# Single_Board_12s.net
KiCad netlist of a schematic drawn in EAGLE
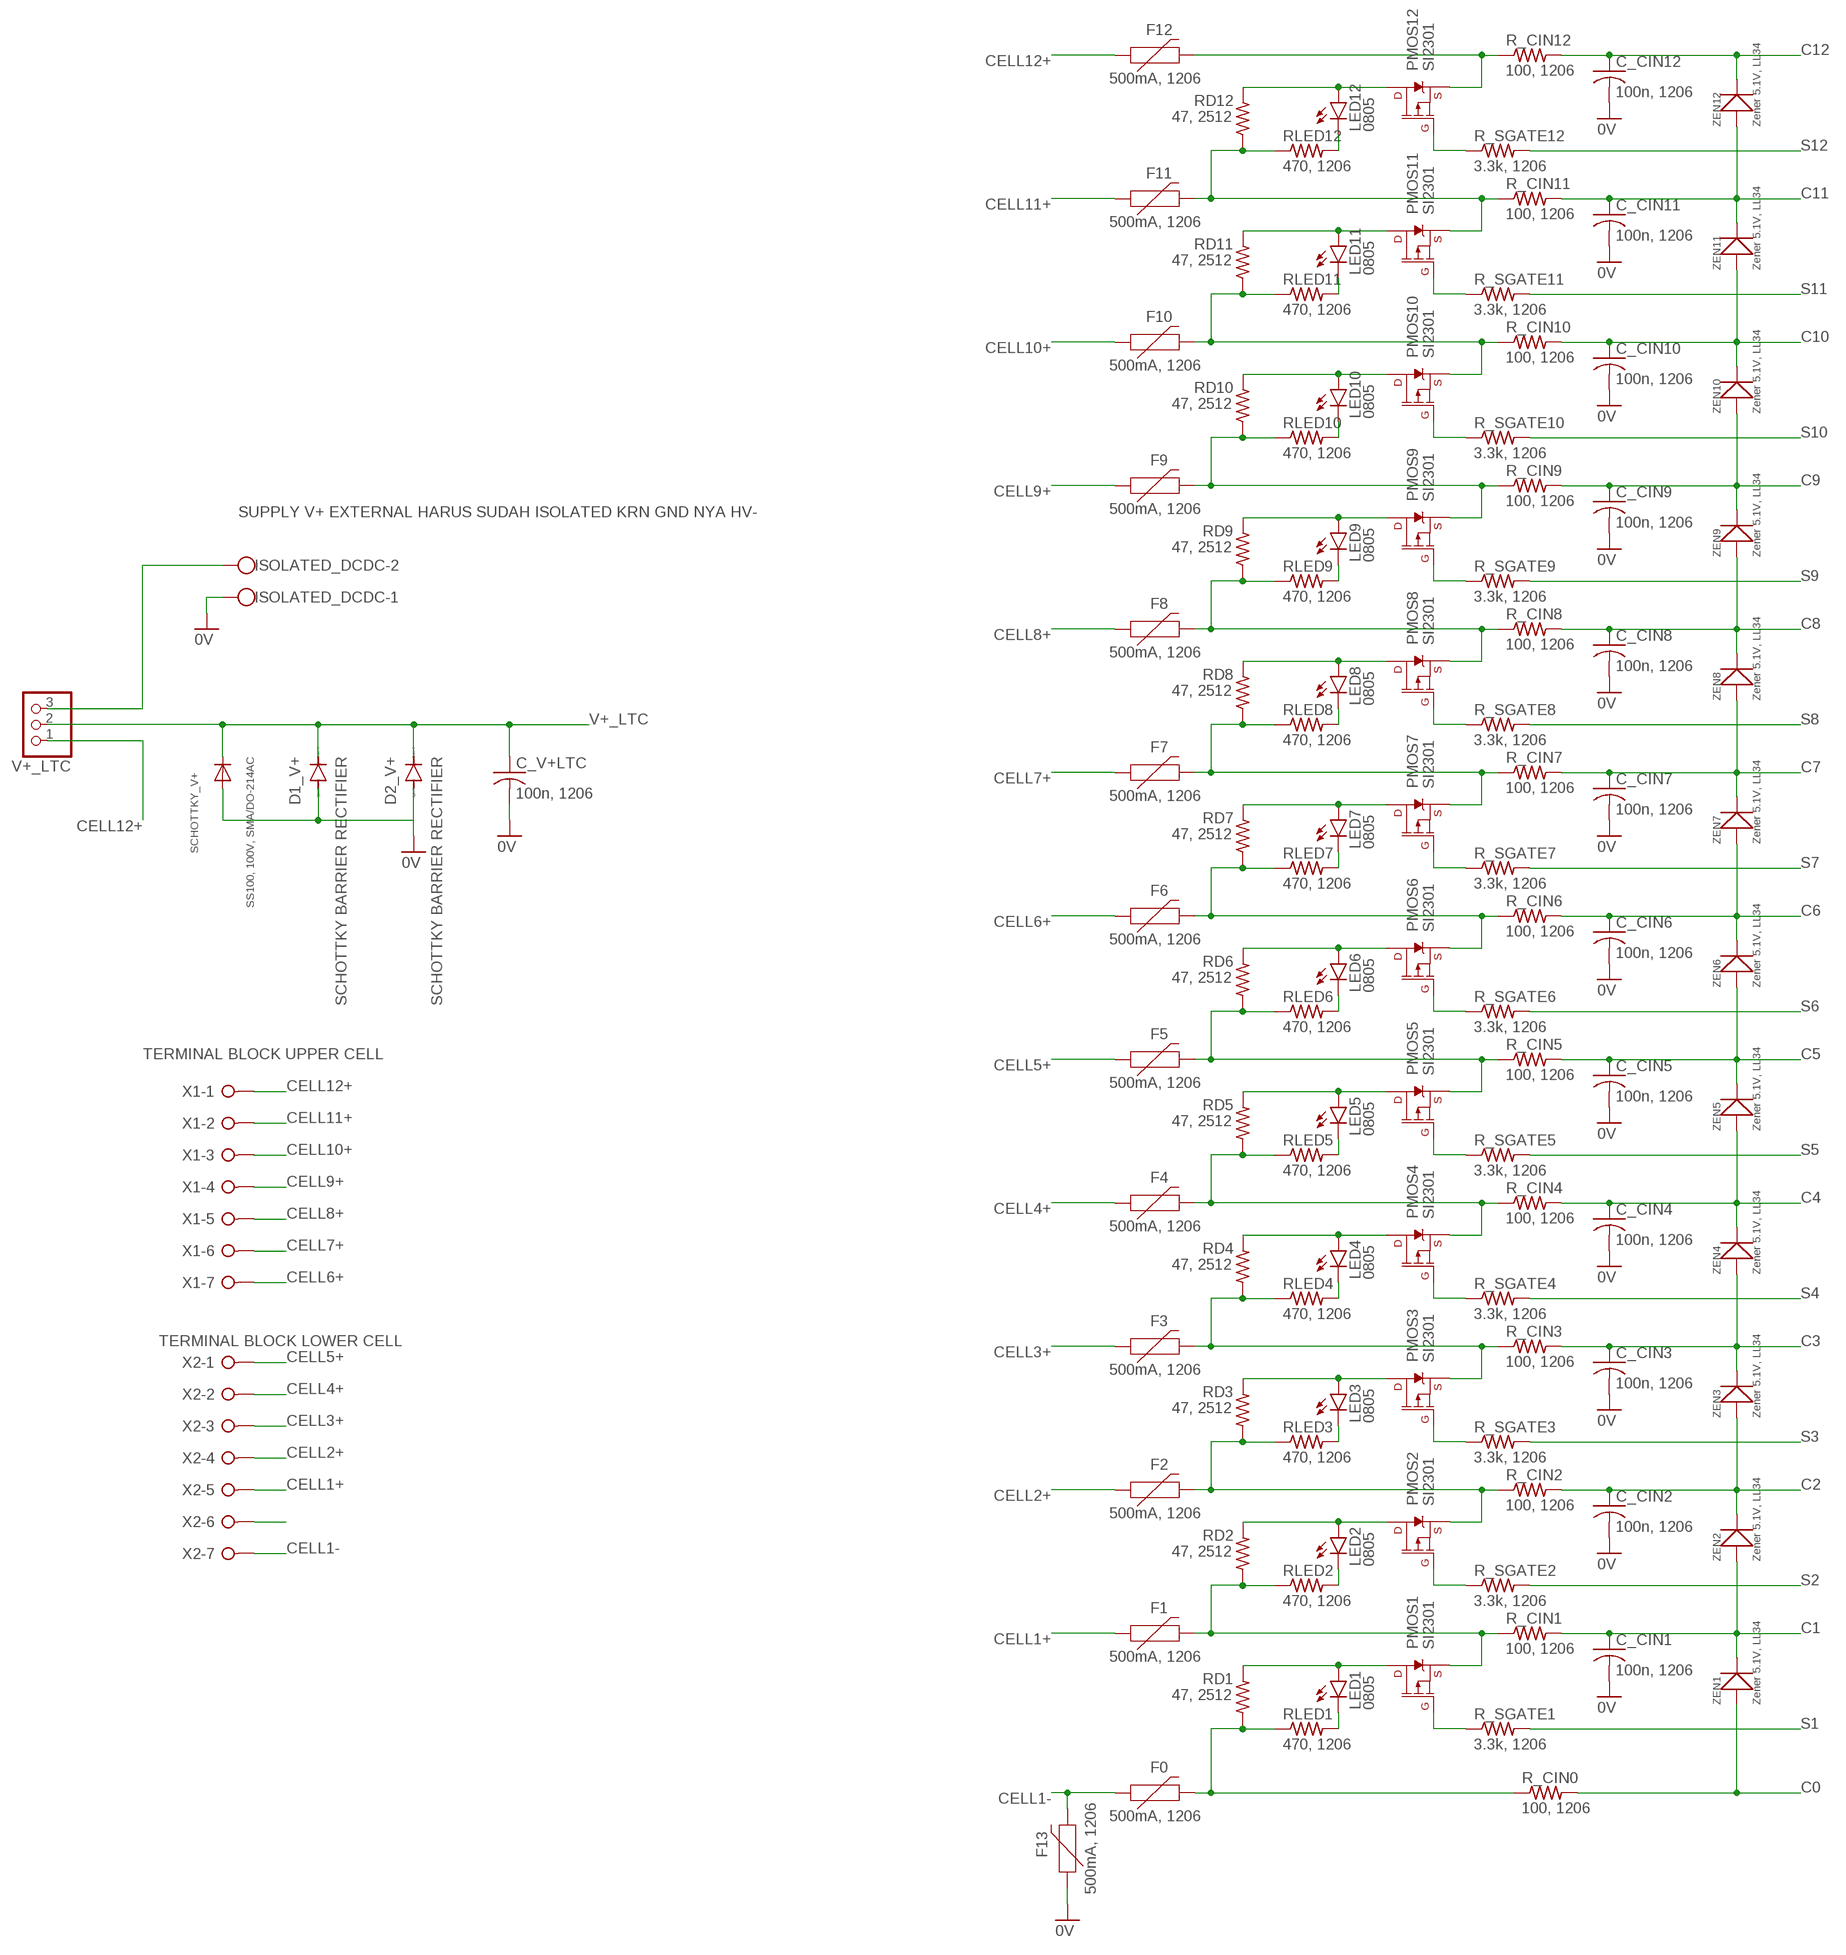
[diagram p0: schematic, sheet 1, part 1 of 2]
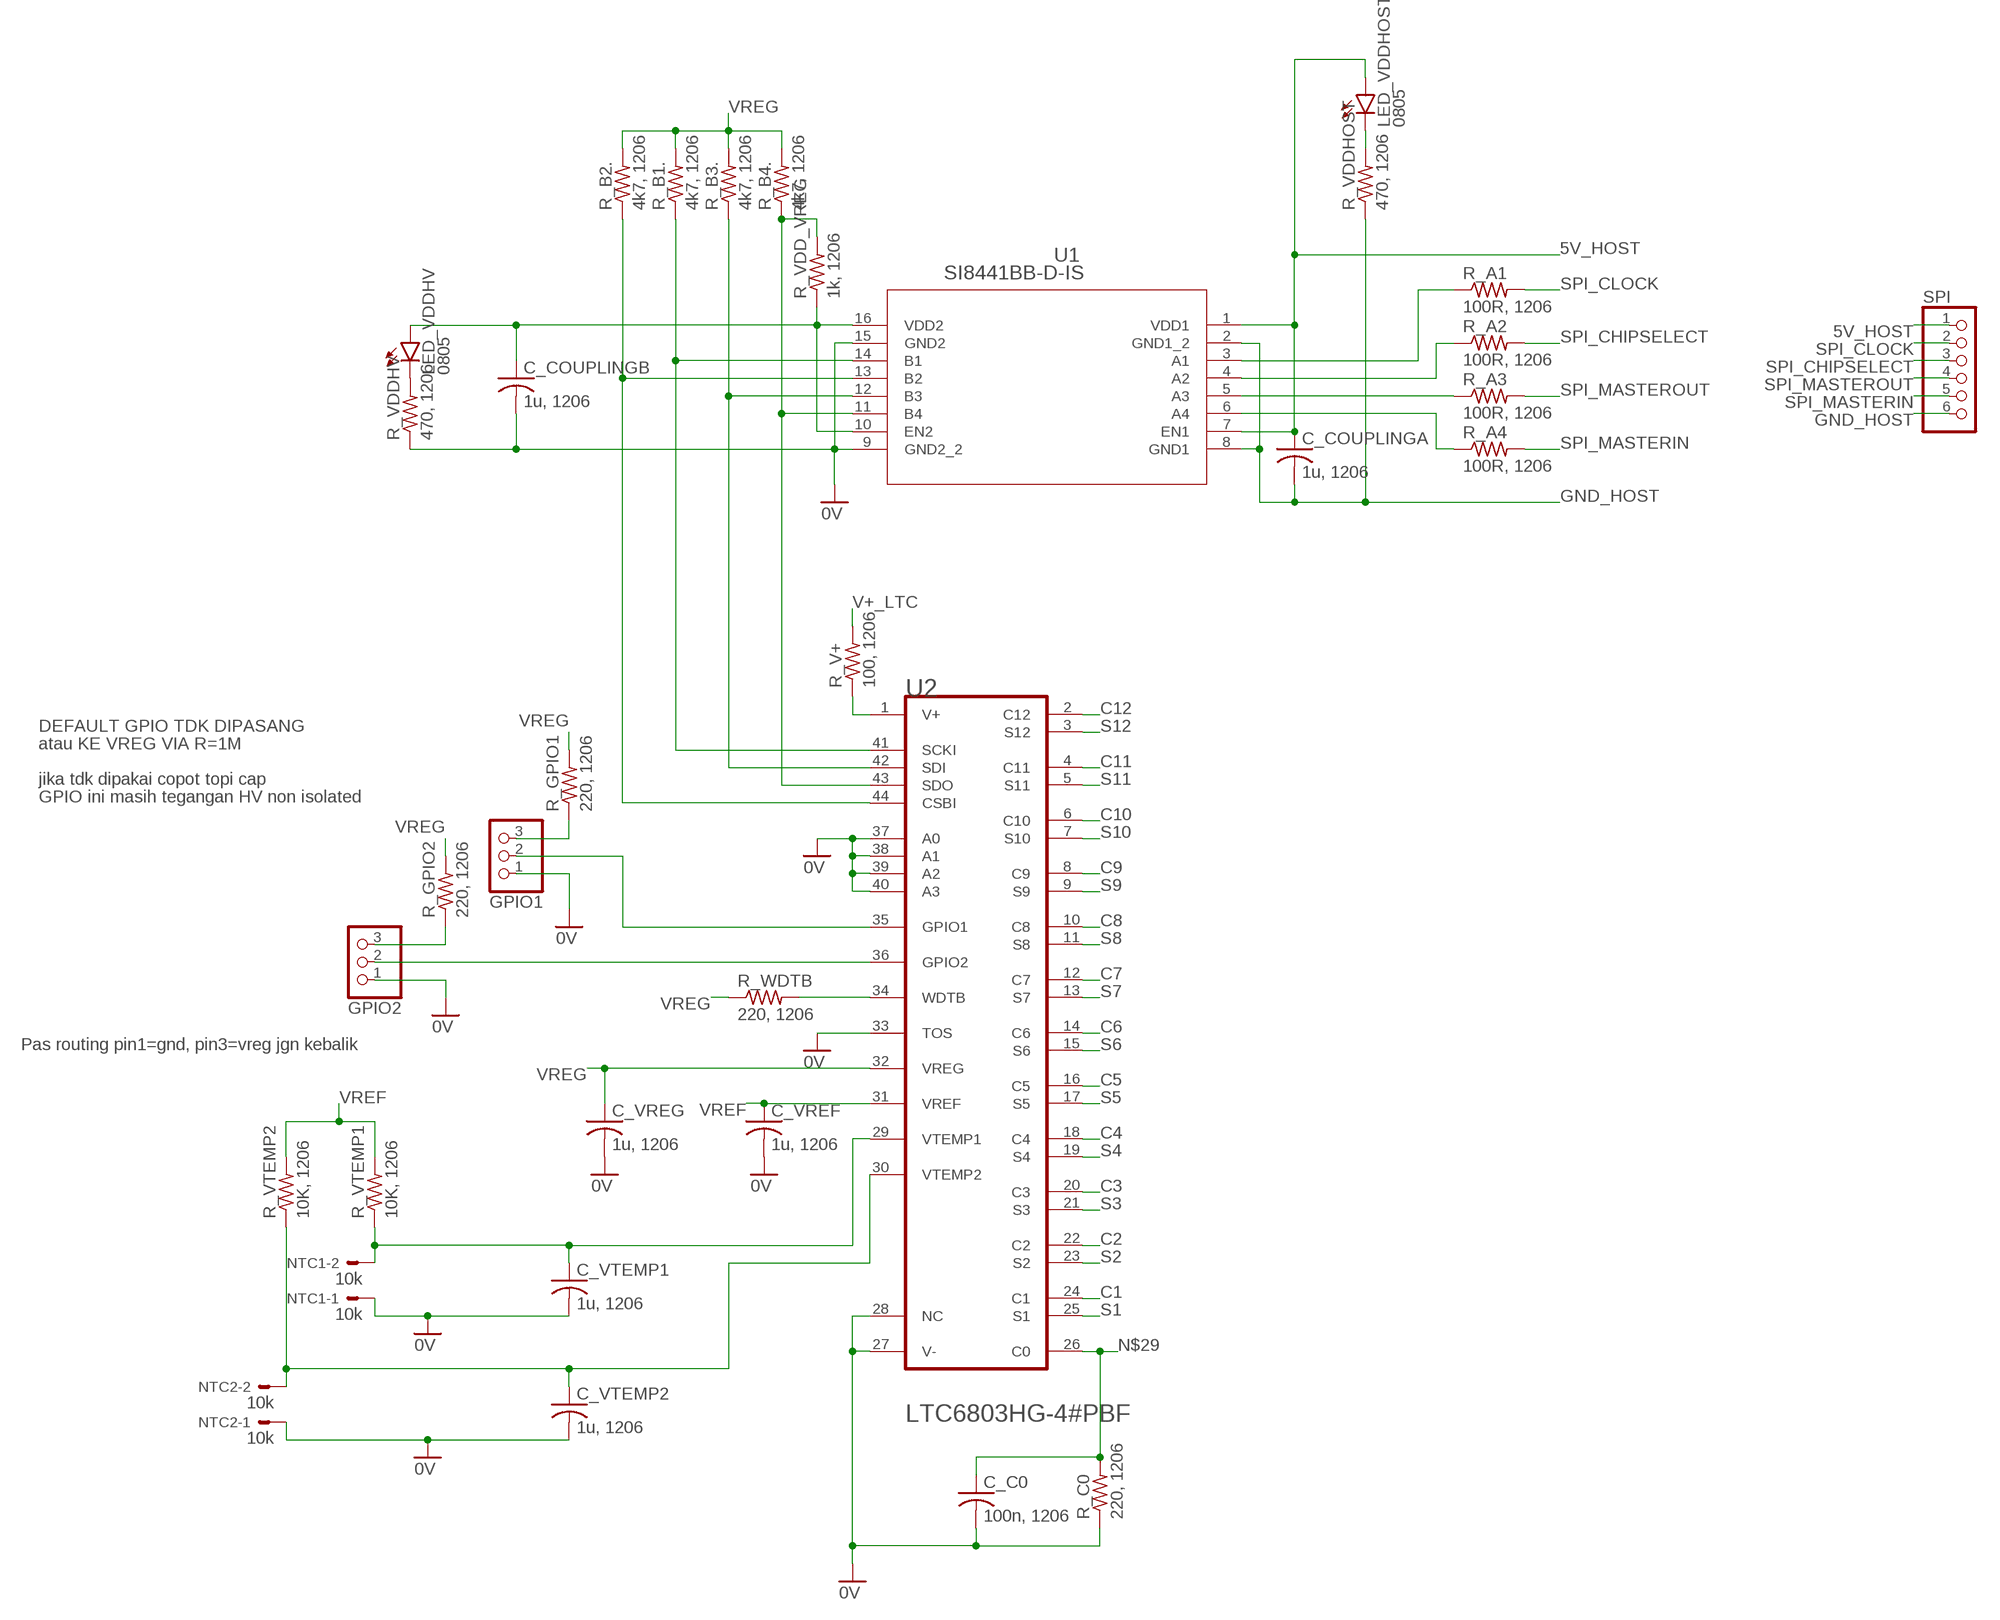
[diagram p1: schematic, sheet 1, part 2 of 2]

(export (version "E")
  (design (tool "Eeschema 10.0.6"))
  (components
    (comp (ref "C_C0")
      (value "100n, 1206")
      (footprint "eagle-import:C1206")
      (libsource (lib "eagle-import") (part "C-USC1206"))
    )
    (comp (ref "C_CIN1")
      (value "100n, 1206")
      (footprint "eagle-import:C1206")
      (libsource (lib "eagle-import") (part "C-USC1206"))
    )
    (comp (ref "C_CIN2")
      (value "100n, 1206")
      (footprint "eagle-import:C1206")
      (libsource (lib "eagle-import") (part "C-USC1206"))
    )
    (comp (ref "C_CIN3")
      (value "100n, 1206")
      (footprint "eagle-import:C1206")
      (libsource (lib "eagle-import") (part "C-USC1206"))
    )
    (comp (ref "C_CIN4")
      (value "100n, 1206")
      (footprint "eagle-import:C1206")
      (libsource (lib "eagle-import") (part "C-USC1206"))
    )
    (comp (ref "C_CIN5")
      (value "100n, 1206")
      (footprint "eagle-import:C1206")
      (libsource (lib "eagle-import") (part "C-USC1206"))
    )
    (comp (ref "C_CIN6")
      (value "100n, 1206")
      (footprint "eagle-import:C1206")
      (libsource (lib "eagle-import") (part "C-USC1206"))
    )
    (comp (ref "C_CIN7")
      (value "100n, 1206")
      (footprint "eagle-import:C1206")
      (libsource (lib "eagle-import") (part "C-USC1206"))
    )
    (comp (ref "C_CIN8")
      (value "100n, 1206")
      (footprint "eagle-import:C1206")
      (libsource (lib "eagle-import") (part "C-USC1206"))
    )
    (comp (ref "C_CIN9")
      (value "100n, 1206")
      (footprint "eagle-import:C1206")
      (libsource (lib "eagle-import") (part "C-USC1206"))
    )
    (comp (ref "C_CIN10")
      (value "100n, 1206")
      (footprint "eagle-import:C1206")
      (libsource (lib "eagle-import") (part "C-USC1206"))
    )
    (comp (ref "C_CIN11")
      (value "100n, 1206")
      (footprint "eagle-import:C1206")
      (libsource (lib "eagle-import") (part "C-USC1206"))
    )
    (comp (ref "C_CIN12")
      (value "100n, 1206")
      (footprint "eagle-import:C1206")
      (libsource (lib "eagle-import") (part "C-USC1206"))
    )
    (comp (ref "C_COUPLINGA")
      (value "1u, 1206")
      (footprint "eagle-import:C1206")
      (libsource (lib "eagle-import") (part "C-USC1206"))
    )
    (comp (ref "C_COUPLINGB")
      (value "1u, 1206")
      (footprint "eagle-import:C1206")
      (libsource (lib "eagle-import") (part "C-USC1206"))
    )
    (comp (ref "C_V+LTC")
      (value "100n, 1206")
      (footprint "eagle-import:C1206")
      (libsource (lib "eagle-import") (part "C-USC1206"))
    )
    (comp (ref "C_VREF")
      (value "1u, 1206")
      (footprint "eagle-import:C1206")
      (libsource (lib "eagle-import") (part "C-USC1206"))
    )
    (comp (ref "C_VREG")
      (value "1u, 1206")
      (footprint "eagle-import:C1206")
      (libsource (lib "eagle-import") (part "C-USC1206"))
    )
    (comp (ref "C_VTEMP1")
      (value "1u, 1206")
      (footprint "eagle-import:C1206")
      (libsource (lib "eagle-import") (part "C-USC1206"))
    )
    (comp (ref "C_VTEMP2")
      (value "1u, 1206")
      (footprint "eagle-import:C1206")
      (libsource (lib "eagle-import") (part "C-USC1206"))
    )
    (comp (ref "D1_V+")
      (value "SCHOTTKY BARRIER RECTIFIER")
      (footprint "eagle-import:DO27-15")
      (libsource (lib "eagle-import") (part "DIODE-DO27-15"))
    )
    (comp (ref "D2_V+")
      (value "SCHOTTKY BARRIER RECTIFIER")
      (footprint "eagle-import:DO27-15")
      (libsource (lib "eagle-import") (part "DIODE-DO27-15"))
    )
    (comp (ref "F0")
      (value "500mA, 1206")
      (footprint "eagle-import:1206")
      (libsource (lib "eagle-import") (part "PPTC_6V500MA-2"))
    )
    (comp (ref "F1")
      (value "500mA, 1206")
      (footprint "eagle-import:1206")
      (libsource (lib "eagle-import") (part "PPTC_6V500MA-2"))
    )
    (comp (ref "F2")
      (value "500mA, 1206")
      (footprint "eagle-import:1206")
      (libsource (lib "eagle-import") (part "PPTC_6V500MA-2"))
    )
    (comp (ref "F3")
      (value "500mA, 1206")
      (footprint "eagle-import:1206")
      (libsource (lib "eagle-import") (part "PPTC_6V500MA-2"))
    )
    (comp (ref "F4")
      (value "500mA, 1206")
      (footprint "eagle-import:1206")
      (libsource (lib "eagle-import") (part "PPTC_6V500MA-2"))
    )
    (comp (ref "F5")
      (value "500mA, 1206")
      (footprint "eagle-import:1206")
      (libsource (lib "eagle-import") (part "PPTC_6V500MA-2"))
    )
    (comp (ref "F6")
      (value "500mA, 1206")
      (footprint "eagle-import:1206")
      (libsource (lib "eagle-import") (part "PPTC_6V500MA-2"))
    )
    (comp (ref "F7")
      (value "500mA, 1206")
      (footprint "eagle-import:1206")
      (libsource (lib "eagle-import") (part "PPTC_6V500MA-2"))
    )
    (comp (ref "F8")
      (value "500mA, 1206")
      (footprint "eagle-import:1206")
      (libsource (lib "eagle-import") (part "PPTC_6V500MA-2"))
    )
    (comp (ref "F9")
      (value "500mA, 1206")
      (footprint "eagle-import:1206")
      (libsource (lib "eagle-import") (part "PPTC_6V500MA-2"))
    )
    (comp (ref "F10")
      (value "500mA, 1206")
      (footprint "eagle-import:1206")
      (libsource (lib "eagle-import") (part "PPTC_6V500MA-2"))
    )
    (comp (ref "F11")
      (value "500mA, 1206")
      (footprint "eagle-import:1206")
      (libsource (lib "eagle-import") (part "PPTC_6V500MA-2"))
    )
    (comp (ref "F12")
      (value "500mA, 1206")
      (footprint "eagle-import:1206")
      (libsource (lib "eagle-import") (part "PPTC_6V500MA-2"))
    )
    (comp (ref "F13")
      (value "500mA, 1206")
      (footprint "eagle-import:1206")
      (libsource (lib "eagle-import") (part "PPTC_6V500MA-2"))
    )
    (comp (ref "GPIO1")
      (value "PINHD-1X3")
      (footprint "eagle-import:1X03")
      (libsource (lib "eagle-import") (part "PINHD-1X3"))
    )
    (comp (ref "GPIO2")
      (value "PINHD-1X3")
      (footprint "eagle-import:1X03")
      (libsource (lib "eagle-import") (part "PINHD-1X3"))
    )
    (comp (ref "ISOLATED_DCDC")
      (value "W237-102")
      (footprint "eagle-import:W237-102")
      (fields (field (name "MPN") "237-102"))
      (libsource (lib "eagle-import") (part "W237-102"))
    )
    (comp (ref "LED1")
      (value "0805")
      (footprint "eagle-import:SML0805")
      (libsource (lib "eagle-import") (part "LEDSML0805"))
    )
    (comp (ref "LED2")
      (value "0805")
      (footprint "eagle-import:SML0805")
      (libsource (lib "eagle-import") (part "LEDSML0805"))
    )
    (comp (ref "LED3")
      (value "0805")
      (footprint "eagle-import:SML0805")
      (libsource (lib "eagle-import") (part "LEDSML0805"))
    )
    (comp (ref "LED4")
      (value "0805")
      (footprint "eagle-import:SML0805")
      (libsource (lib "eagle-import") (part "LEDSML0805"))
    )
    (comp (ref "LED5")
      (value "0805")
      (footprint "eagle-import:SML0805")
      (libsource (lib "eagle-import") (part "LEDSML0805"))
    )
    (comp (ref "LED6")
      (value "0805")
      (footprint "eagle-import:SML0805")
      (libsource (lib "eagle-import") (part "LEDSML0805"))
    )
    (comp (ref "LED7")
      (value "0805")
      (footprint "eagle-import:SML0805")
      (libsource (lib "eagle-import") (part "LEDSML0805"))
    )
    (comp (ref "LED8")
      (value "0805")
      (footprint "eagle-import:SML0805")
      (libsource (lib "eagle-import") (part "LEDSML0805"))
    )
    (comp (ref "LED9")
      (value "0805")
      (footprint "eagle-import:SML0805")
      (libsource (lib "eagle-import") (part "LEDSML0805"))
    )
    (comp (ref "LED10")
      (value "0805")
      (footprint "eagle-import:SML0805")
      (libsource (lib "eagle-import") (part "LEDSML0805"))
    )
    (comp (ref "LED11")
      (value "0805")
      (footprint "eagle-import:SML0805")
      (libsource (lib "eagle-import") (part "LEDSML0805"))
    )
    (comp (ref "LED12")
      (value "0805")
      (footprint "eagle-import:SML0805")
      (libsource (lib "eagle-import") (part "LEDSML0805"))
    )
    (comp (ref "LED_VDDHOST")
      (value "0805")
      (footprint "eagle-import:SML0805")
      (libsource (lib "eagle-import") (part "LEDSML0805"))
    )
    (comp (ref "LED_VDDHV")
      (value "0805")
      (footprint "eagle-import:SML0805")
      (libsource (lib "eagle-import") (part "LEDSML0805"))
    )
    (comp (ref "NTC1")
      (value "10k")
      (footprint "eagle-import:KK-156-2")
      (fields (field (name "MF") "MOLEX"))
      (libsource (lib "eagle-import") (part "KK-156-2"))
    )
    (comp (ref "NTC2")
      (value "10k")
      (footprint "eagle-import:KK-156-2")
      (fields (field (name "MF") "MOLEX"))
      (libsource (lib "eagle-import") (part "KK-156-2"))
    )
    (comp (ref "PMOS1")
      (value "SI2301")
      (footprint "eagle-import:SOT23-3")
      (libsource (lib "eagle-import") (part "MOSFET_PCH-SI2309DS"))
    )
    (comp (ref "PMOS2")
      (value "SI2301")
      (footprint "eagle-import:SOT23-3")
      (libsource (lib "eagle-import") (part "MOSFET_PCH-SI2309DS"))
    )
    (comp (ref "PMOS3")
      (value "SI2301")
      (footprint "eagle-import:SOT23-3")
      (libsource (lib "eagle-import") (part "MOSFET_PCH-SI2309DS"))
    )
    (comp (ref "PMOS4")
      (value "SI2301")
      (footprint "eagle-import:SOT23-3")
      (libsource (lib "eagle-import") (part "MOSFET_PCH-SI2309DS"))
    )
    (comp (ref "PMOS5")
      (value "SI2301")
      (footprint "eagle-import:SOT23-3")
      (libsource (lib "eagle-import") (part "MOSFET_PCH-SI2309DS"))
    )
    (comp (ref "PMOS6")
      (value "SI2301")
      (footprint "eagle-import:SOT23-3")
      (libsource (lib "eagle-import") (part "MOSFET_PCH-SI2309DS"))
    )
    (comp (ref "PMOS7")
      (value "SI2301")
      (footprint "eagle-import:SOT23-3")
      (libsource (lib "eagle-import") (part "MOSFET_PCH-SI2309DS"))
    )
    (comp (ref "PMOS8")
      (value "SI2301")
      (footprint "eagle-import:SOT23-3")
      (libsource (lib "eagle-import") (part "MOSFET_PCH-SI2309DS"))
    )
    (comp (ref "PMOS9")
      (value "SI2301")
      (footprint "eagle-import:SOT23-3")
      (libsource (lib "eagle-import") (part "MOSFET_PCH-SI2309DS"))
    )
    (comp (ref "PMOS10")
      (value "SI2301")
      (footprint "eagle-import:SOT23-3")
      (libsource (lib "eagle-import") (part "MOSFET_PCH-SI2309DS"))
    )
    (comp (ref "PMOS11")
      (value "SI2301")
      (footprint "eagle-import:SOT23-3")
      (libsource (lib "eagle-import") (part "MOSFET_PCH-SI2309DS"))
    )
    (comp (ref "PMOS12")
      (value "SI2301")
      (footprint "eagle-import:SOT23-3")
      (libsource (lib "eagle-import") (part "MOSFET_PCH-SI2309DS"))
    )
    (comp (ref "RD1")
      (value "47, 2512")
      (footprint "eagle-import:R2512")
      (libsource (lib "eagle-import") (part "R-US_R2512"))
    )
    (comp (ref "RD2")
      (value "47, 2512")
      (footprint "eagle-import:R2512")
      (libsource (lib "eagle-import") (part "R-US_R2512"))
    )
    (comp (ref "RD3")
      (value "47, 2512")
      (footprint "eagle-import:R2512")
      (libsource (lib "eagle-import") (part "R-US_R2512"))
    )
    (comp (ref "RD4")
      (value "47, 2512")
      (footprint "eagle-import:R2512")
      (libsource (lib "eagle-import") (part "R-US_R2512"))
    )
    (comp (ref "RD5")
      (value "47, 2512")
      (footprint "eagle-import:R2512")
      (libsource (lib "eagle-import") (part "R-US_R2512"))
    )
    (comp (ref "RD6")
      (value "47, 2512")
      (footprint "eagle-import:R2512")
      (libsource (lib "eagle-import") (part "R-US_R2512"))
    )
    (comp (ref "RD7")
      (value "47, 2512")
      (footprint "eagle-import:R2512")
      (libsource (lib "eagle-import") (part "R-US_R2512"))
    )
    (comp (ref "RD8")
      (value "47, 2512")
      (footprint "eagle-import:R2512")
      (libsource (lib "eagle-import") (part "R-US_R2512"))
    )
    (comp (ref "RD9")
      (value "47, 2512")
      (footprint "eagle-import:R2512")
      (libsource (lib "eagle-import") (part "R-US_R2512"))
    )
    (comp (ref "RD10")
      (value "47, 2512")
      (footprint "eagle-import:R2512")
      (libsource (lib "eagle-import") (part "R-US_R2512"))
    )
    (comp (ref "RD11")
      (value "47, 2512")
      (footprint "eagle-import:R2512")
      (libsource (lib "eagle-import") (part "R-US_R2512"))
    )
    (comp (ref "RD12")
      (value "47, 2512")
      (footprint "eagle-import:R2512")
      (libsource (lib "eagle-import") (part "R-US_R2512"))
    )
    (comp (ref "RLED1")
      (value "470, 1206")
      (footprint "eagle-import:R1206")
      (libsource (lib "eagle-import") (part "R-US_R1206"))
    )
    (comp (ref "RLED2")
      (value "470, 1206")
      (footprint "eagle-import:R1206")
      (libsource (lib "eagle-import") (part "R-US_R1206"))
    )
    (comp (ref "RLED3")
      (value "470, 1206")
      (footprint "eagle-import:R1206")
      (libsource (lib "eagle-import") (part "R-US_R1206"))
    )
    (comp (ref "RLED4")
      (value "470, 1206")
      (footprint "eagle-import:R1206")
      (libsource (lib "eagle-import") (part "R-US_R1206"))
    )
    (comp (ref "RLED5")
      (value "470, 1206")
      (footprint "eagle-import:R1206")
      (libsource (lib "eagle-import") (part "R-US_R1206"))
    )
    (comp (ref "RLED6")
      (value "470, 1206")
      (footprint "eagle-import:R1206")
      (libsource (lib "eagle-import") (part "R-US_R1206"))
    )
    (comp (ref "RLED7")
      (value "470, 1206")
      (footprint "eagle-import:R1206")
      (libsource (lib "eagle-import") (part "R-US_R1206"))
    )
    (comp (ref "RLED8")
      (value "470, 1206")
      (footprint "eagle-import:R1206")
      (libsource (lib "eagle-import") (part "R-US_R1206"))
    )
    (comp (ref "RLED9")
      (value "470, 1206")
      (footprint "eagle-import:R1206")
      (libsource (lib "eagle-import") (part "R-US_R1206"))
    )
    (comp (ref "RLED10")
      (value "470, 1206")
      (footprint "eagle-import:R1206")
      (libsource (lib "eagle-import") (part "R-US_R1206"))
    )
    (comp (ref "RLED11")
      (value "470, 1206")
      (footprint "eagle-import:R1206")
      (libsource (lib "eagle-import") (part "R-US_R1206"))
    )
    (comp (ref "RLED12")
      (value "470, 1206")
      (footprint "eagle-import:R1206")
      (libsource (lib "eagle-import") (part "R-US_R1206"))
    )
    (comp (ref "R_A1")
      (value "100R, 1206")
      (footprint "eagle-import:R1206")
      (libsource (lib "eagle-import") (part "R-US_R1206"))
    )
    (comp (ref "R_A2")
      (value "100R, 1206")
      (footprint "eagle-import:R1206")
      (libsource (lib "eagle-import") (part "R-US_R1206"))
    )
    (comp (ref "R_A3")
      (value "100R, 1206")
      (footprint "eagle-import:R1206")
      (libsource (lib "eagle-import") (part "R-US_R1206"))
    )
    (comp (ref "R_A4")
      (value "100R, 1206")
      (footprint "eagle-import:R1206")
      (libsource (lib "eagle-import") (part "R-US_R1206"))
    )
    (comp (ref "R_B1.")
      (value "4k7, 1206")
      (footprint "eagle-import:R1206")
      (libsource (lib "eagle-import") (part "R-US_R1206"))
    )
    (comp (ref "R_B2.")
      (value "4k7, 1206")
      (footprint "eagle-import:R1206")
      (libsource (lib "eagle-import") (part "R-US_R1206"))
    )
    (comp (ref "R_B3.")
      (value "4k7, 1206")
      (footprint "eagle-import:R1206")
      (libsource (lib "eagle-import") (part "R-US_R1206"))
    )
    (comp (ref "R_B4.")
      (value "4k7, 1206")
      (footprint "eagle-import:R1206")
      (libsource (lib "eagle-import") (part "R-US_R1206"))
    )
    (comp (ref "R_C0")
      (value "220, 1206")
      (footprint "eagle-import:R1206")
      (libsource (lib "eagle-import") (part "R-US_R1206"))
    )
    (comp (ref "R_CIN0")
      (value "100, 1206")
      (footprint "eagle-import:R1206")
      (libsource (lib "eagle-import") (part "R-US_R1206"))
    )
    (comp (ref "R_CIN1")
      (value "100, 1206")
      (footprint "eagle-import:R1206")
      (libsource (lib "eagle-import") (part "R-US_R1206"))
    )
    (comp (ref "R_CIN2")
      (value "100, 1206")
      (footprint "eagle-import:R1206")
      (libsource (lib "eagle-import") (part "R-US_R1206"))
    )
    (comp (ref "R_CIN3")
      (value "100, 1206")
      (footprint "eagle-import:R1206")
      (libsource (lib "eagle-import") (part "R-US_R1206"))
    )
    (comp (ref "R_CIN4")
      (value "100, 1206")
      (footprint "eagle-import:R1206")
      (libsource (lib "eagle-import") (part "R-US_R1206"))
    )
    (comp (ref "R_CIN5")
      (value "100, 1206")
      (footprint "eagle-import:R1206")
      (libsource (lib "eagle-import") (part "R-US_R1206"))
    )
    (comp (ref "R_CIN6")
      (value "100, 1206")
      (footprint "eagle-import:R1206")
      (libsource (lib "eagle-import") (part "R-US_R1206"))
    )
    (comp (ref "R_CIN7")
      (value "100, 1206")
      (footprint "eagle-import:R1206")
      (libsource (lib "eagle-import") (part "R-US_R1206"))
    )
    (comp (ref "R_CIN8")
      (value "100, 1206")
      (footprint "eagle-import:R1206")
      (libsource (lib "eagle-import") (part "R-US_R1206"))
    )
    (comp (ref "R_CIN9")
      (value "100, 1206")
      (footprint "eagle-import:R1206")
      (libsource (lib "eagle-import") (part "R-US_R1206"))
    )
    (comp (ref "R_CIN10")
      (value "100, 1206")
      (footprint "eagle-import:R1206")
      (libsource (lib "eagle-import") (part "R-US_R1206"))
    )
    (comp (ref "R_CIN11")
      (value "100, 1206")
      (footprint "eagle-import:R1206")
      (libsource (lib "eagle-import") (part "R-US_R1206"))
    )
    (comp (ref "R_CIN12")
      (value "100, 1206")
      (footprint "eagle-import:R1206")
      (libsource (lib "eagle-import") (part "R-US_R1206"))
    )
    (comp (ref "R_GPIO1")
      (value "220, 1206")
      (footprint "eagle-import:R1206")
      (libsource (lib "eagle-import") (part "R-US_R1206"))
    )
    (comp (ref "R_GPIO2")
      (value "220, 1206")
      (footprint "eagle-import:R1206")
      (libsource (lib "eagle-import") (part "R-US_R1206"))
    )
    (comp (ref "R_SGATE1")
      (value "3.3k, 1206")
      (footprint "eagle-import:R1206")
      (libsource (lib "eagle-import") (part "R-US_R1206"))
    )
    (comp (ref "R_SGATE2")
      (value "3.3k, 1206")
      (footprint "eagle-import:R1206")
      (libsource (lib "eagle-import") (part "R-US_R1206"))
    )
    (comp (ref "R_SGATE3")
      (value "3.3k, 1206")
      (footprint "eagle-import:R1206")
      (libsource (lib "eagle-import") (part "R-US_R1206"))
    )
    (comp (ref "R_SGATE4")
      (value "3.3k, 1206")
      (footprint "eagle-import:R1206")
      (libsource (lib "eagle-import") (part "R-US_R1206"))
    )
    (comp (ref "R_SGATE5")
      (value "3.3k, 1206")
      (footprint "eagle-import:R1206")
      (libsource (lib "eagle-import") (part "R-US_R1206"))
    )
    (comp (ref "R_SGATE6")
      (value "3.3k, 1206")
      (footprint "eagle-import:R1206")
      (libsource (lib "eagle-import") (part "R-US_R1206"))
    )
    (comp (ref "R_SGATE7")
      (value "3.3k, 1206")
      (footprint "eagle-import:R1206")
      (libsource (lib "eagle-import") (part "R-US_R1206"))
    )
    (comp (ref "R_SGATE8")
      (value "3.3k, 1206")
      (footprint "eagle-import:R1206")
      (libsource (lib "eagle-import") (part "R-US_R1206"))
    )
    (comp (ref "R_SGATE9")
      (value "3.3k, 1206")
      (footprint "eagle-import:R1206")
      (libsource (lib "eagle-import") (part "R-US_R1206"))
    )
    (comp (ref "R_SGATE10")
      (value "3.3k, 1206")
      (footprint "eagle-import:R1206")
      (libsource (lib "eagle-import") (part "R-US_R1206"))
    )
    (comp (ref "R_SGATE11")
      (value "3.3k, 1206")
      (footprint "eagle-import:R1206")
      (libsource (lib "eagle-import") (part "R-US_R1206"))
    )
    (comp (ref "R_SGATE12")
      (value "3.3k, 1206")
      (footprint "eagle-import:R1206")
      (libsource (lib "eagle-import") (part "R-US_R1206"))
    )
    (comp (ref "R_V+")
      (value "100, 1206")
      (footprint "eagle-import:R1206")
      (libsource (lib "eagle-import") (part "R-US_R1206"))
    )
    (comp (ref "R_VDDHOST")
      (value "470, 1206")
      (footprint "eagle-import:R1206")
      (libsource (lib "eagle-import") (part "R-US_R1206"))
    )
    (comp (ref "R_VDDHV")
      (value "470, 1206")
      (footprint "eagle-import:R1206")
      (libsource (lib "eagle-import") (part "R-US_R1206"))
    )
    (comp (ref "R_VDD_VREG")
      (value "1k, 1206")
      (footprint "eagle-import:R1206")
      (libsource (lib "eagle-import") (part "R-US_R1206"))
    )
    (comp (ref "R_VTEMP1")
      (value "10K, 1206")
      (footprint "eagle-import:R1206")
      (libsource (lib "eagle-import") (part "R-US_R1206"))
    )
    (comp (ref "R_VTEMP2")
      (value "10K, 1206")
      (footprint "eagle-import:R1206")
      (libsource (lib "eagle-import") (part "R-US_R1206"))
    )
    (comp (ref "R_WDTB")
      (value "220, 1206")
      (footprint "eagle-import:R1206")
      (libsource (lib "eagle-import") (part "R-US_R1206"))
    )
    (comp (ref "SCHOTTKY_V+")
      (value "SS100, 100V, SMA/DO-214AC")
      (footprint "eagle-import:SMADIODE")
      (libsource (lib "eagle-import") (part "DIODESMA"))
    )
    (comp (ref "SPI")
      (value "PINHD-1X6")
      (footprint "eagle-import:1X06")
      (libsource (lib "eagle-import") (part "PINHD-1X6"))
    )
    (comp (ref "U1")
      (value "SI8441BB-D-IS")
      (footprint "eagle-import:SOIC-16W_SIL")
      (fields (field (name "COPYRIGHT") "Copyright (C) 2021 Ultra Librarian. All rights reserved."))
      (libsource (lib "eagle-import") (part "SI8441BB-D-IS"))
    )
    (comp (ref "U2")
      (value "LINEAR_TECHNOLOGY_LTC6803HG-4#PBFLINEAR_TECHNOLOGY_LTC6803HG-4#PBF_0_2")
      (footprint "eagle-import:LINEAR_TECHNOLOGY_LTC6803HG-4#PBF_2")
      (fields (field (name "MF") "Linear Technology") (field (name "MPN") "LTC6803HG-4#PBF"))
      (libsource (lib "eagle-import") (part "LINEAR_TECHNOLOGY_LTC6803HG-4#PBFLINEAR_TECHNOLOGY_LTC6803HG-4#PBF_0_2"))
    )
    (comp (ref "V+_LTC")
      (value "PINHD-1X3")
      (footprint "eagle-import:1X03")
      (libsource (lib "eagle-import") (part "PINHD-1X3"))
    )
    (comp (ref "X1")
      (value "W237-07P")
      (footprint "eagle-import:W237-7P")
      (libsource (lib "eagle-import") (part "W237-07P"))
    )
    (comp (ref "X2")
      (value "W237-07P")
      (footprint "eagle-import:W237-7P")
      (libsource (lib "eagle-import") (part "W237-07P"))
    )
    (comp (ref "ZEN1")
      (value "Zener 5.1V, LL34")
      (footprint "eagle-import:LL-34")
      (fields (field (name "MPN") "LL4148ST"))
      (libsource (lib "eagle-import") (part "SMD-DIODE-SWITCHING-75V-200MA(LL-34)"))
    )
    (comp (ref "ZEN2")
      (value "Zener 5.1V, LL34")
      (footprint "eagle-import:LL-34")
      (fields (field (name "MPN") "LL4148ST"))
      (libsource (lib "eagle-import") (part "SMD-DIODE-SWITCHING-75V-200MA(LL-34)"))
    )
    (comp (ref "ZEN3")
      (value "Zener 5.1V, LL34")
      (footprint "eagle-import:LL-34")
      (fields (field (name "MPN") "LL4148ST"))
      (libsource (lib "eagle-import") (part "SMD-DIODE-SWITCHING-75V-200MA(LL-34)"))
    )
    (comp (ref "ZEN4")
      (value "Zener 5.1V, LL34")
      (footprint "eagle-import:LL-34")
      (fields (field (name "MPN") "LL4148ST"))
      (libsource (lib "eagle-import") (part "SMD-DIODE-SWITCHING-75V-200MA(LL-34)"))
    )
    (comp (ref "ZEN5")
      (value "Zener 5.1V, LL34")
      (footprint "eagle-import:LL-34")
      (fields (field (name "MPN") "LL4148ST"))
      (libsource (lib "eagle-import") (part "SMD-DIODE-SWITCHING-75V-200MA(LL-34)"))
    )
    (comp (ref "ZEN6")
      (value "Zener 5.1V, LL34")
      (footprint "eagle-import:LL-34")
      (fields (field (name "MPN") "LL4148ST"))
      (libsource (lib "eagle-import") (part "SMD-DIODE-SWITCHING-75V-200MA(LL-34)"))
    )
    (comp (ref "ZEN7")
      (value "Zener 5.1V, LL34")
      (footprint "eagle-import:LL-34")
      (fields (field (name "MPN") "LL4148ST"))
      (libsource (lib "eagle-import") (part "SMD-DIODE-SWITCHING-75V-200MA(LL-34)"))
    )
    (comp (ref "ZEN8")
      (value "Zener 5.1V, LL34")
      (footprint "eagle-import:LL-34")
      (fields (field (name "MPN") "LL4148ST"))
      (libsource (lib "eagle-import") (part "SMD-DIODE-SWITCHING-75V-200MA(LL-34)"))
    )
    (comp (ref "ZEN9")
      (value "Zener 5.1V, LL34")
      (footprint "eagle-import:LL-34")
      (fields (field (name "MPN") "LL4148ST"))
      (libsource (lib "eagle-import") (part "SMD-DIODE-SWITCHING-75V-200MA(LL-34)"))
    )
    (comp (ref "ZEN10")
      (value "Zener 5.1V, LL34")
      (footprint "eagle-import:LL-34")
      (fields (field (name "MPN") "LL4148ST"))
      (libsource (lib "eagle-import") (part "SMD-DIODE-SWITCHING-75V-200MA(LL-34)"))
    )
    (comp (ref "ZEN11")
      (value "Zener 5.1V, LL34")
      (footprint "eagle-import:LL-34")
      (fields (field (name "MPN") "LL4148ST"))
      (libsource (lib "eagle-import") (part "SMD-DIODE-SWITCHING-75V-200MA(LL-34)"))
    )
    (comp (ref "ZEN12")
      (value "Zener 5.1V, LL34")
      (footprint "eagle-import:LL-34")
      (fields (field (name "MPN") "LL4148ST"))
      (libsource (lib "eagle-import") (part "SMD-DIODE-SWITCHING-75V-200MA(LL-34)"))
    )
  )
  (nets
    (net (code "1") (name "/5V_HOST") (class "Default")
      (node (ref "C_COUPLINGA") (pin "1") (pinfunction "1_1") (pintype "passive"))
      (node (ref "LED_VDDHOST") (pin "A") (pinfunction "A_A") (pintype "passive"))
      (node (ref "SPI") (pin "1") (pinfunction "1_1") (pintype "passive"))
      (node (ref "U1") (pin "1") (pinfunction "VDD1_1") (pintype "passive"))
      (node (ref "U1") (pin "7") (pinfunction "EN1_7") (pintype "input"))
    )
    (net (code "2") (name "/C0") (class "Default")
      (node (ref "R_CIN0") (pin "2") (pinfunction "2_2") (pintype "passive"))
      (node (ref "ZEN1") (pin "A") (pinfunction "+_A") (pintype "passive"))
    )
    (net (code "3") (name "/C1") (class "Default")
      (node (ref "C_CIN1") (pin "1") (pinfunction "1_1") (pintype "passive"))
      (node (ref "R_CIN1") (pin "2") (pinfunction "2_2") (pintype "passive"))
      (node (ref "U2") (pin "24") (pinfunction "C1_24") (pintype "input"))
      (node (ref "ZEN1") (pin "C") (pinfunction "-_C") (pintype "passive"))
      (node (ref "ZEN2") (pin "A") (pinfunction "+_A") (pintype "passive"))
    )
    (net (code "4") (name "/C2") (class "Default")
      (node (ref "C_CIN2") (pin "1") (pinfunction "1_1") (pintype "passive"))
      (node (ref "R_CIN2") (pin "2") (pinfunction "2_2") (pintype "passive"))
      (node (ref "U2") (pin "22") (pinfunction "C2_22") (pintype "input"))
      (node (ref "ZEN2") (pin "C") (pinfunction "-_C") (pintype "passive"))
      (node (ref "ZEN3") (pin "A") (pinfunction "+_A") (pintype "passive"))
    )
    (net (code "5") (name "/C3") (class "Default")
      (node (ref "C_CIN3") (pin "1") (pinfunction "1_1") (pintype "passive"))
      (node (ref "R_CIN3") (pin "2") (pinfunction "2_2") (pintype "passive"))
      (node (ref "U2") (pin "20") (pinfunction "C3_20") (pintype "input"))
      (node (ref "ZEN3") (pin "C") (pinfunction "-_C") (pintype "passive"))
      (node (ref "ZEN4") (pin "A") (pinfunction "+_A") (pintype "passive"))
    )
    (net (code "6") (name "/C4") (class "Default")
      (node (ref "C_CIN4") (pin "1") (pinfunction "1_1") (pintype "passive"))
      (node (ref "R_CIN4") (pin "2") (pinfunction "2_2") (pintype "passive"))
      (node (ref "U2") (pin "18") (pinfunction "C4_18") (pintype "input"))
      (node (ref "ZEN4") (pin "C") (pinfunction "-_C") (pintype "passive"))
      (node (ref "ZEN5") (pin "A") (pinfunction "+_A") (pintype "passive"))
    )
    (net (code "7") (name "/C5") (class "Default")
      (node (ref "C_CIN5") (pin "1") (pinfunction "1_1") (pintype "passive"))
      (node (ref "R_CIN5") (pin "2") (pinfunction "2_2") (pintype "passive"))
      (node (ref "U2") (pin "16") (pinfunction "C5_16") (pintype "input"))
      (node (ref "ZEN5") (pin "C") (pinfunction "-_C") (pintype "passive"))
      (node (ref "ZEN6") (pin "A") (pinfunction "+_A") (pintype "passive"))
    )
    (net (code "8") (name "/C6") (class "Default")
      (node (ref "C_CIN6") (pin "1") (pinfunction "1_1") (pintype "passive"))
      (node (ref "R_CIN6") (pin "2") (pinfunction "2_2") (pintype "passive"))
      (node (ref "U2") (pin "14") (pinfunction "C6_14") (pintype "input"))
      (node (ref "ZEN6") (pin "C") (pinfunction "-_C") (pintype "passive"))
      (node (ref "ZEN7") (pin "A") (pinfunction "+_A") (pintype "passive"))
    )
    (net (code "9") (name "/C7") (class "Default")
      (node (ref "C_CIN7") (pin "1") (pinfunction "1_1") (pintype "passive"))
      (node (ref "R_CIN7") (pin "2") (pinfunction "2_2") (pintype "passive"))
      (node (ref "U2") (pin "12") (pinfunction "C7_12") (pintype "input"))
      (node (ref "ZEN7") (pin "C") (pinfunction "-_C") (pintype "passive"))
      (node (ref "ZEN8") (pin "A") (pinfunction "+_A") (pintype "passive"))
    )
    (net (code "10") (name "/C8") (class "Default")
      (node (ref "C_CIN8") (pin "1") (pinfunction "1_1") (pintype "passive"))
      (node (ref "R_CIN8") (pin "2") (pinfunction "2_2") (pintype "passive"))
      (node (ref "U2") (pin "10") (pinfunction "C8_10") (pintype "input"))
      (node (ref "ZEN8") (pin "C") (pinfunction "-_C") (pintype "passive"))
      (node (ref "ZEN9") (pin "A") (pinfunction "+_A") (pintype "passive"))
    )
    (net (code "11") (name "/C9") (class "Default")
      (node (ref "C_CIN9") (pin "1") (pinfunction "1_1") (pintype "passive"))
      (node (ref "R_CIN9") (pin "2") (pinfunction "2_2") (pintype "passive"))
      (node (ref "U2") (pin "8") (pinfunction "C9_8") (pintype "input"))
      (node (ref "ZEN10") (pin "A") (pinfunction "+_A") (pintype "passive"))
      (node (ref "ZEN9") (pin "C") (pinfunction "-_C") (pintype "passive"))
    )
    (net (code "12") (name "/C10") (class "Default")
      (node (ref "C_CIN10") (pin "1") (pinfunction "1_1") (pintype "passive"))
      (node (ref "R_CIN10") (pin "2") (pinfunction "2_2") (pintype "passive"))
      (node (ref "U2") (pin "6") (pinfunction "C10_6") (pintype "input"))
      (node (ref "ZEN10") (pin "C") (pinfunction "-_C") (pintype "passive"))
      (node (ref "ZEN11") (pin "A") (pinfunction "+_A") (pintype "passive"))
    )
    (net (code "13") (name "/C11") (class "Default")
      (node (ref "C_CIN11") (pin "1") (pinfunction "1_1") (pintype "passive"))
      (node (ref "R_CIN11") (pin "2") (pinfunction "2_2") (pintype "passive"))
      (node (ref "U2") (pin "4") (pinfunction "C11_4") (pintype "input"))
      (node (ref "ZEN11") (pin "C") (pinfunction "-_C") (pintype "passive"))
      (node (ref "ZEN12") (pin "A") (pinfunction "+_A") (pintype "passive"))
    )
    (net (code "14") (name "/C12") (class "Default")
      (node (ref "C_CIN12") (pin "1") (pinfunction "1_1") (pintype "passive"))
      (node (ref "R_CIN12") (pin "2") (pinfunction "2_2") (pintype "passive"))
      (node (ref "U2") (pin "2") (pinfunction "C12_2") (pintype "input"))
      (node (ref "ZEN12") (pin "C") (pinfunction "-_C") (pintype "passive"))
    )
    (net (code "15") (name "/CELL1+") (class "Default")
      (node (ref "F1") (pin "1") (pinfunction "1_1") (pintype "bidirectional"))
      (node (ref "X2") (pin "5") (pinfunction "KL_5") (pintype "passive"))
    )
    (net (code "16") (name "/CELL1-") (class "Default")
      (node (ref "F0") (pin "1") (pinfunction "1_1") (pintype "bidirectional"))
      (node (ref "F13") (pin "2") (pinfunction "2_2") (pintype "bidirectional"))
      (node (ref "X2") (pin "7") (pinfunction "KL_7") (pintype "passive"))
    )
    (net (code "17") (name "/CELL2+") (class "Default")
      (node (ref "F2") (pin "1") (pinfunction "1_1") (pintype "bidirectional"))
      (node (ref "X2") (pin "4") (pinfunction "KL_4") (pintype "passive"))
    )
    (net (code "18") (name "/CELL3+") (class "Default")
      (node (ref "F3") (pin "1") (pinfunction "1_1") (pintype "bidirectional"))
      (node (ref "X2") (pin "3") (pinfunction "KL_3") (pintype "passive"))
    )
    (net (code "19") (name "/CELL4+") (class "Default")
      (node (ref "F4") (pin "1") (pinfunction "1_1") (pintype "bidirectional"))
      (node (ref "X2") (pin "2") (pinfunction "KL_2") (pintype "passive"))
    )
    (net (code "20") (name "/CELL5+") (class "Default")
      (node (ref "F5") (pin "1") (pinfunction "1_1") (pintype "bidirectional"))
      (node (ref "X2") (pin "1") (pinfunction "KL_1") (pintype "passive"))
    )
    (net (code "21") (name "/CELL6+") (class "Default")
      (node (ref "F6") (pin "1") (pinfunction "1_1") (pintype "bidirectional"))
      (node (ref "X1") (pin "7") (pinfunction "KL_7") (pintype "passive"))
    )
    (net (code "22") (name "/CELL7+") (class "Default")
      (node (ref "F7") (pin "1") (pinfunction "1_1") (pintype "bidirectional"))
      (node (ref "X1") (pin "6") (pinfunction "KL_6") (pintype "passive"))
    )
    (net (code "23") (name "/CELL8+") (class "Default")
      (node (ref "F8") (pin "1") (pinfunction "1_1") (pintype "bidirectional"))
      (node (ref "X1") (pin "5") (pinfunction "KL_5") (pintype "passive"))
    )
    (net (code "24") (name "/CELL9+") (class "Default")
      (node (ref "F9") (pin "1") (pinfunction "1_1") (pintype "bidirectional"))
      (node (ref "X1") (pin "4") (pinfunction "KL_4") (pintype "passive"))
    )
    (net (code "25") (name "/CELL10+") (class "Default")
      (node (ref "F10") (pin "1") (pinfunction "1_1") (pintype "bidirectional"))
      (node (ref "X1") (pin "3") (pinfunction "KL_3") (pintype "passive"))
    )
    (net (code "26") (name "/CELL11+") (class "Default")
      (node (ref "F11") (pin "1") (pinfunction "1_1") (pintype "bidirectional"))
      (node (ref "X1") (pin "2") (pinfunction "KL_2") (pintype "passive"))
    )
    (net (code "27") (name "/CELL12+") (class "Default")
      (node (ref "F12") (pin "1") (pinfunction "1_1") (pintype "bidirectional"))
      (node (ref "V+_LTC") (pin "1") (pinfunction "1_1") (pintype "passive"))
      (node (ref "X1") (pin "1") (pinfunction "KL_1") (pintype "passive"))
    )
    (net (code "28") (name "/GND_HOST") (class "Default")
      (node (ref "C_COUPLINGA") (pin "2") (pinfunction "2_2") (pintype "passive"))
      (node (ref "R_VDDHOST") (pin "1") (pinfunction "1_1") (pintype "passive"))
      (node (ref "SPI") (pin "6") (pinfunction "6_6") (pintype "passive"))
      (node (ref "U1") (pin "2") (pinfunction "GND1_2_2") (pintype "passive"))
      (node (ref "U1") (pin "8") (pinfunction "GND1_8") (pintype "passive"))
    )
    (net (code "29") (name "/N$29") (class "Default")
      (node (ref "C_C0") (pin "1") (pinfunction "1_1") (pintype "passive"))
      (node (ref "R_C0") (pin "2") (pinfunction "2_2") (pintype "passive"))
      (node (ref "U2") (pin "26") (pinfunction "C0_26") (pintype "input"))
    )
    (net (code "30") (name "/S1") (class "Default")
      (node (ref "R_SGATE1") (pin "2") (pinfunction "2_2") (pintype "passive"))
      (node (ref "U2") (pin "25") (pinfunction "S1_25") (pintype "tri_state"))
    )
    (net (code "31") (name "/S2") (class "Default")
      (node (ref "R_SGATE2") (pin "2") (pinfunction "2_2") (pintype "passive"))
      (node (ref "U2") (pin "23") (pinfunction "S2_23") (pintype "tri_state"))
    )
    (net (code "32") (name "/S3") (class "Default")
      (node (ref "R_SGATE3") (pin "2") (pinfunction "2_2") (pintype "passive"))
      (node (ref "U2") (pin "21") (pinfunction "S3_21") (pintype "tri_state"))
    )
    (net (code "33") (name "/S4") (class "Default")
      (node (ref "R_SGATE4") (pin "2") (pinfunction "2_2") (pintype "passive"))
      (node (ref "U2") (pin "19") (pinfunction "S4_19") (pintype "tri_state"))
    )
    (net (code "34") (name "/S5") (class "Default")
      (node (ref "R_SGATE5") (pin "2") (pinfunction "2_2") (pintype "passive"))
      (node (ref "U2") (pin "17") (pinfunction "S5_17") (pintype "tri_state"))
    )
    (net (code "35") (name "/S6") (class "Default")
      (node (ref "R_SGATE6") (pin "2") (pinfunction "2_2") (pintype "passive"))
      (node (ref "U2") (pin "15") (pinfunction "S6_15") (pintype "tri_state"))
    )
    (net (code "36") (name "/S7") (class "Default")
      (node (ref "R_SGATE7") (pin "2") (pinfunction "2_2") (pintype "passive"))
      (node (ref "U2") (pin "13") (pinfunction "S7_13") (pintype "tri_state"))
    )
    (net (code "37") (name "/S8") (class "Default")
      (node (ref "R_SGATE8") (pin "2") (pinfunction "2_2") (pintype "passive"))
      (node (ref "U2") (pin "11") (pinfunction "S8_11") (pintype "tri_state"))
    )
    (net (code "38") (name "/S9") (class "Default")
      (node (ref "R_SGATE9") (pin "2") (pinfunction "2_2") (pintype "passive"))
      (node (ref "U2") (pin "9") (pinfunction "S9_9") (pintype "tri_state"))
    )
    (net (code "39") (name "/S10") (class "Default")
      (node (ref "R_SGATE10") (pin "2") (pinfunction "2_2") (pintype "passive"))
      (node (ref "U2") (pin "7") (pinfunction "S10_7") (pintype "tri_state"))
    )
    (net (code "40") (name "/S11") (class "Default")
      (node (ref "R_SGATE11") (pin "2") (pinfunction "2_2") (pintype "passive"))
      (node (ref "U2") (pin "5") (pinfunction "S11_5") (pintype "tri_state"))
    )
    (net (code "41") (name "/S12") (class "Default")
      (node (ref "R_SGATE12") (pin "2") (pinfunction "2_2") (pintype "passive"))
      (node (ref "U2") (pin "3") (pinfunction "S12_3") (pintype "tri_state"))
    )
    (net (code "42") (name "/SPI_CHIPSELECT") (class "Default")
      (node (ref "R_A2") (pin "2") (pinfunction "2_2") (pintype "passive"))
      (node (ref "SPI") (pin "3") (pinfunction "3_3") (pintype "passive"))
    )
    (net (code "43") (name "/SPI_CLOCK") (class "Default")
      (node (ref "R_A1") (pin "2") (pinfunction "2_2") (pintype "passive"))
      (node (ref "SPI") (pin "2") (pinfunction "2_2") (pintype "passive"))
    )
    (net (code "44") (name "/SPI_MASTERIN") (class "Default")
      (node (ref "R_A4") (pin "2") (pinfunction "2_2") (pintype "passive"))
      (node (ref "SPI") (pin "5") (pinfunction "5_5") (pintype "passive"))
    )
    (net (code "45") (name "/SPI_MASTEROUT") (class "Default")
      (node (ref "R_A3") (pin "2") (pinfunction "2_2") (pintype "passive"))
      (node (ref "SPI") (pin "4") (pinfunction "4_4") (pintype "passive"))
    )
    (net (code "46") (name "/V+_LTC") (class "Default")
      (node (ref "C_V+LTC") (pin "1") (pinfunction "1_1") (pintype "passive"))
      (node (ref "D1_V+") (pin "C") (pinfunction "C_C") (pintype "passive"))
      (node (ref "D2_V+") (pin "C") (pinfunction "C_C") (pintype "passive"))
      (node (ref "R_V+") (pin "2") (pinfunction "2_2") (pintype "passive"))
      (node (ref "SCHOTTKY_V+") (pin "C") (pinfunction "C_C") (pintype "passive"))
      (node (ref "V+_LTC") (pin "2") (pinfunction "2_2") (pintype "passive"))
    )
    (net (code "47") (name "/VREF") (class "Default")
      (node (ref "C_VREF") (pin "1") (pinfunction "1_1") (pintype "passive"))
      (node (ref "R_VTEMP1") (pin "2") (pinfunction "2_2") (pintype "passive"))
      (node (ref "R_VTEMP2") (pin "2") (pinfunction "2_2") (pintype "passive"))
      (node (ref "U2") (pin "31") (pinfunction "VREF_31") (pintype "output"))
    )
    (net (code "48") (name "/VREG") (class "Default")
      (node (ref "C_COUPLINGB") (pin "1") (pinfunction "1_1") (pintype "passive"))
      (node (ref "C_VREG") (pin "1") (pinfunction "1_1") (pintype "passive"))
      (node (ref "LED_VDDHV") (pin "A") (pinfunction "A_A") (pintype "passive"))
      (node (ref "R_B1.") (pin "2") (pinfunction "2_2") (pintype "passive"))
      (node (ref "R_B2.") (pin "2") (pinfunction "2_2") (pintype "passive"))
      (node (ref "R_B3.") (pin "2") (pinfunction "2_2") (pintype "passive"))
      (node (ref "R_B4.") (pin "2") (pinfunction "2_2") (pintype "passive"))
      (node (ref "R_GPIO1") (pin "2") (pinfunction "2_2") (pintype "passive"))
      (node (ref "R_GPIO2") (pin "2") (pinfunction "2_2") (pintype "passive"))
      (node (ref "R_VDD_VREG") (pin "1") (pinfunction "1_1") (pintype "passive"))
      (node (ref "R_WDTB") (pin "1") (pinfunction "1_1") (pintype "passive"))
      (node (ref "U1") (pin "10") (pinfunction "EN2_10") (pintype "input"))
      (node (ref "U1") (pin "16") (pinfunction "VDD2_16") (pintype "passive"))
      (node (ref "U2") (pin "32") (pinfunction "VREG_32") (pintype "power_in"))
    )
    (net (code "49") (name "0V") (class "Default")
      (node (ref "C_C0") (pin "2") (pinfunction "2_2") (pintype "passive"))
      (node (ref "C_CIN1") (pin "2") (pinfunction "2_2") (pintype "passive"))
      (node (ref "C_CIN10") (pin "2") (pinfunction "2_2") (pintype "passive"))
      (node (ref "C_CIN11") (pin "2") (pinfunction "2_2") (pintype "passive"))
      (node (ref "C_CIN12") (pin "2") (pinfunction "2_2") (pintype "passive"))
      (node (ref "C_CIN2") (pin "2") (pinfunction "2_2") (pintype "passive"))
      (node (ref "C_CIN3") (pin "2") (pinfunction "2_2") (pintype "passive"))
      (node (ref "C_CIN4") (pin "2") (pinfunction "2_2") (pintype "passive"))
      (node (ref "C_CIN5") (pin "2") (pinfunction "2_2") (pintype "passive"))
      (node (ref "C_CIN6") (pin "2") (pinfunction "2_2") (pintype "passive"))
      (node (ref "C_CIN7") (pin "2") (pinfunction "2_2") (pintype "passive"))
      (node (ref "C_CIN8") (pin "2") (pinfunction "2_2") (pintype "passive"))
      (node (ref "C_CIN9") (pin "2") (pinfunction "2_2") (pintype "passive"))
      (node (ref "C_COUPLINGB") (pin "2") (pinfunction "2_2") (pintype "passive"))
      (node (ref "C_V+LTC") (pin "2") (pinfunction "2_2") (pintype "passive"))
      (node (ref "C_VREF") (pin "2") (pinfunction "2_2") (pintype "passive"))
      (node (ref "C_VREG") (pin "2") (pinfunction "2_2") (pintype "passive"))
      (node (ref "C_VTEMP1") (pin "2") (pinfunction "2_2") (pintype "passive"))
      (node (ref "C_VTEMP2") (pin "2") (pinfunction "2_2") (pintype "passive"))
      (node (ref "D1_V+") (pin "A") (pinfunction "A_A") (pintype "passive"))
      (node (ref "D2_V+") (pin "A") (pinfunction "A_A") (pintype "passive"))
      (node (ref "F13") (pin "1") (pinfunction "1_1") (pintype "bidirectional"))
      (node (ref "GPIO1") (pin "1") (pinfunction "1_1") (pintype "passive"))
      (node (ref "GPIO2") (pin "1") (pinfunction "1_1") (pintype "passive"))
      (node (ref "ISOLATED_DCDC") (pin "1") (pinfunction "KL_1") (pintype "passive"))
      (node (ref "NTC1") (pin "1") (pinfunction "S_1") (pintype "passive"))
      (node (ref "NTC2") (pin "1") (pinfunction "S_1") (pintype "passive"))
      (node (ref "R_C0") (pin "1") (pinfunction "1_1") (pintype "passive"))
      (node (ref "R_VDDHV") (pin "1") (pinfunction "1_1") (pintype "passive"))
      (node (ref "SCHOTTKY_V+") (pin "A") (pinfunction "A_A") (pintype "passive"))
      (node (ref "U1") (pin "15") (pinfunction "GND2_15") (pintype "passive"))
      (node (ref "U1") (pin "9") (pinfunction "GND2_2_9") (pintype "passive"))
      (node (ref "U2") (pin "27") (pinfunction "V-_27") (pintype "power_in"))
      (node (ref "U2") (pin "28") (pinfunction "NC_28") (pintype "passive"))
      (node (ref "U2") (pin "33") (pinfunction "TOS_33") (pintype "input"))
      (node (ref "U2") (pin "37") (pinfunction "A0_37") (pintype "input"))
      (node (ref "U2") (pin "38") (pinfunction "A1_38") (pintype "input"))
      (node (ref "U2") (pin "39") (pinfunction "A2_39") (pintype "input"))
      (node (ref "U2") (pin "40") (pinfunction "A3_40") (pintype "input"))
    )
    (net (code "50") (name "Net-(F0-Pad2)") (class "Default")
      (node (ref "F0") (pin "2") (pinfunction "2_2") (pintype "bidirectional"))
      (node (ref "RD1") (pin "1") (pinfunction "1_1") (pintype "passive"))
      (node (ref "RLED1") (pin "1") (pinfunction "1_1") (pintype "passive"))
      (node (ref "R_CIN0") (pin "1") (pinfunction "1_1") (pintype "passive"))
    )
    (net (code "51") (name "Net-(GPIO1-Pad3)") (class "Default")
      (node (ref "GPIO1") (pin "3") (pinfunction "3_3") (pintype "passive"))
      (node (ref "R_GPIO1") (pin "1") (pinfunction "1_1") (pintype "passive"))
    )
    (net (code "52") (name "Net-(GPIO2-Pad3)") (class "Default")
      (node (ref "GPIO2") (pin "3") (pinfunction "3_3") (pintype "passive"))
      (node (ref "R_GPIO2") (pin "1") (pinfunction "1_1") (pintype "passive"))
    )
    (net (code "53") (name "Net-(ISOLATED_DCDCB-KL)") (class "Default")
      (node (ref "ISOLATED_DCDC") (pin "2") (pinfunction "KL_2") (pintype "passive"))
      (node (ref "V+_LTC") (pin "3") (pinfunction "3_3") (pintype "passive"))
    )
    (net (code "54") (name "Net-(LED1-PadC)") (class "Default")
      (node (ref "LED1") (pin "C") (pinfunction "C_C") (pintype "passive"))
      (node (ref "RLED1") (pin "2") (pinfunction "2_2") (pintype "passive"))
    )
    (net (code "55") (name "Net-(LED2-PadC)") (class "Default")
      (node (ref "LED2") (pin "C") (pinfunction "C_C") (pintype "passive"))
      (node (ref "RLED2") (pin "2") (pinfunction "2_2") (pintype "passive"))
    )
    (net (code "56") (name "Net-(LED3-PadC)") (class "Default")
      (node (ref "LED3") (pin "C") (pinfunction "C_C") (pintype "passive"))
      (node (ref "RLED3") (pin "2") (pinfunction "2_2") (pintype "passive"))
    )
    (net (code "57") (name "Net-(LED4-PadC)") (class "Default")
      (node (ref "LED4") (pin "C") (pinfunction "C_C") (pintype "passive"))
      (node (ref "RLED4") (pin "2") (pinfunction "2_2") (pintype "passive"))
    )
    (net (code "58") (name "Net-(LED5-PadC)") (class "Default")
      (node (ref "LED5") (pin "C") (pinfunction "C_C") (pintype "passive"))
      (node (ref "RLED5") (pin "2") (pinfunction "2_2") (pintype "passive"))
    )
    (net (code "59") (name "Net-(LED6-PadC)") (class "Default")
      (node (ref "LED6") (pin "C") (pinfunction "C_C") (pintype "passive"))
      (node (ref "RLED6") (pin "2") (pinfunction "2_2") (pintype "passive"))
    )
    (net (code "60") (name "Net-(LED7-PadC)") (class "Default")
      (node (ref "LED7") (pin "C") (pinfunction "C_C") (pintype "passive"))
      (node (ref "RLED7") (pin "2") (pinfunction "2_2") (pintype "passive"))
    )
    (net (code "61") (name "Net-(LED8-PadC)") (class "Default")
      (node (ref "LED8") (pin "C") (pinfunction "C_C") (pintype "passive"))
      (node (ref "RLED8") (pin "2") (pinfunction "2_2") (pintype "passive"))
    )
    (net (code "62") (name "Net-(LED9-PadC)") (class "Default")
      (node (ref "LED9") (pin "C") (pinfunction "C_C") (pintype "passive"))
      (node (ref "RLED9") (pin "2") (pinfunction "2_2") (pintype "passive"))
    )
    (net (code "63") (name "Net-(LED10-PadC)") (class "Default")
      (node (ref "LED10") (pin "C") (pinfunction "C_C") (pintype "passive"))
      (node (ref "RLED10") (pin "2") (pinfunction "2_2") (pintype "passive"))
    )
    (net (code "64") (name "Net-(LED11-PadC)") (class "Default")
      (node (ref "LED11") (pin "C") (pinfunction "C_C") (pintype "passive"))
      (node (ref "RLED11") (pin "2") (pinfunction "2_2") (pintype "passive"))
    )
    (net (code "65") (name "Net-(LED12-PadC)") (class "Default")
      (node (ref "LED12") (pin "C") (pinfunction "C_C") (pintype "passive"))
      (node (ref "RLED12") (pin "2") (pinfunction "2_2") (pintype "passive"))
    )
    (net (code "66") (name "Net-(LED_VDDHOST-PadC)") (class "Default")
      (node (ref "LED_VDDHOST") (pin "C") (pinfunction "C_C") (pintype "passive"))
      (node (ref "R_VDDHOST") (pin "2") (pinfunction "2_2") (pintype "passive"))
    )
    (net (code "67") (name "Net-(LED_VDDHV-PadC)") (class "Default")
      (node (ref "LED_VDDHV") (pin "C") (pinfunction "C_C") (pintype "passive"))
      (node (ref "R_VDDHV") (pin "2") (pinfunction "2_2") (pintype "passive"))
    )
    (net (code "68") (name "Net-(NTC1B-S)") (class "Default")
      (node (ref "C_VTEMP1") (pin "1") (pinfunction "1_1") (pintype "passive"))
      (node (ref "NTC1") (pin "2") (pinfunction "S_2") (pintype "passive"))
      (node (ref "R_VTEMP1") (pin "1") (pinfunction "1_1") (pintype "passive"))
      (node (ref "U2") (pin "29") (pinfunction "VTEMP1_29") (pintype "input"))
    )
    (net (code "69") (name "Net-(NTC2B-S)") (class "Default")
      (node (ref "C_VTEMP2") (pin "1") (pinfunction "1_1") (pintype "passive"))
      (node (ref "NTC2") (pin "2") (pinfunction "S_2") (pintype "passive"))
      (node (ref "R_VTEMP2") (pin "1") (pinfunction "1_1") (pintype "passive"))
      (node (ref "U2") (pin "30") (pinfunction "VTEMP2_30") (pintype "input"))
    )
    (net (code "70") (name "Net-(PMOS1-D)") (class "Default")
      (node (ref "LED1") (pin "A") (pinfunction "A_A") (pintype "passive"))
      (node (ref "PMOS1") (pin "3") (pinfunction "D_3") (pintype "bidirectional"))
      (node (ref "RD1") (pin "2") (pinfunction "2_2") (pintype "passive"))
    )
    (net (code "71") (name "Net-(PMOS1-G)") (class "Default")
      (node (ref "PMOS1") (pin "1") (pinfunction "G_1") (pintype "bidirectional"))
      (node (ref "R_SGATE1") (pin "1") (pinfunction "1_1") (pintype "passive"))
    )
    (net (code "72") (name "Net-(PMOS1-S)") (class "Default")
      (node (ref "F1") (pin "2") (pinfunction "2_2") (pintype "bidirectional"))
      (node (ref "PMOS1") (pin "2") (pinfunction "S_2") (pintype "bidirectional"))
      (node (ref "RD2") (pin "1") (pinfunction "1_1") (pintype "passive"))
      (node (ref "RLED2") (pin "1") (pinfunction "1_1") (pintype "passive"))
      (node (ref "R_CIN1") (pin "1") (pinfunction "1_1") (pintype "passive"))
    )
    (net (code "73") (name "Net-(PMOS2-D)") (class "Default")
      (node (ref "LED2") (pin "A") (pinfunction "A_A") (pintype "passive"))
      (node (ref "PMOS2") (pin "3") (pinfunction "D_3") (pintype "bidirectional"))
      (node (ref "RD2") (pin "2") (pinfunction "2_2") (pintype "passive"))
    )
    (net (code "74") (name "Net-(PMOS2-G)") (class "Default")
      (node (ref "PMOS2") (pin "1") (pinfunction "G_1") (pintype "bidirectional"))
      (node (ref "R_SGATE2") (pin "1") (pinfunction "1_1") (pintype "passive"))
    )
    (net (code "75") (name "Net-(PMOS2-S)") (class "Default")
      (node (ref "F2") (pin "2") (pinfunction "2_2") (pintype "bidirectional"))
      (node (ref "PMOS2") (pin "2") (pinfunction "S_2") (pintype "bidirectional"))
      (node (ref "RD3") (pin "1") (pinfunction "1_1") (pintype "passive"))
      (node (ref "RLED3") (pin "1") (pinfunction "1_1") (pintype "passive"))
      (node (ref "R_CIN2") (pin "1") (pinfunction "1_1") (pintype "passive"))
    )
    (net (code "76") (name "Net-(PMOS3-D)") (class "Default")
      (node (ref "LED3") (pin "A") (pinfunction "A_A") (pintype "passive"))
      (node (ref "PMOS3") (pin "3") (pinfunction "D_3") (pintype "bidirectional"))
      (node (ref "RD3") (pin "2") (pinfunction "2_2") (pintype "passive"))
    )
    (net (code "77") (name "Net-(PMOS3-G)") (class "Default")
      (node (ref "PMOS3") (pin "1") (pinfunction "G_1") (pintype "bidirectional"))
      (node (ref "R_SGATE3") (pin "1") (pinfunction "1_1") (pintype "passive"))
    )
    (net (code "78") (name "Net-(PMOS3-S)") (class "Default")
      (node (ref "F3") (pin "2") (pinfunction "2_2") (pintype "bidirectional"))
      (node (ref "PMOS3") (pin "2") (pinfunction "S_2") (pintype "bidirectional"))
      (node (ref "RD4") (pin "1") (pinfunction "1_1") (pintype "passive"))
      (node (ref "RLED4") (pin "1") (pinfunction "1_1") (pintype "passive"))
      (node (ref "R_CIN3") (pin "1") (pinfunction "1_1") (pintype "passive"))
    )
    (net (code "79") (name "Net-(PMOS4-D)") (class "Default")
      (node (ref "LED4") (pin "A") (pinfunction "A_A") (pintype "passive"))
      (node (ref "PMOS4") (pin "3") (pinfunction "D_3") (pintype "bidirectional"))
      (node (ref "RD4") (pin "2") (pinfunction "2_2") (pintype "passive"))
    )
    (net (code "80") (name "Net-(PMOS4-G)") (class "Default")
      (node (ref "PMOS4") (pin "1") (pinfunction "G_1") (pintype "bidirectional"))
      (node (ref "R_SGATE4") (pin "1") (pinfunction "1_1") (pintype "passive"))
    )
    (net (code "81") (name "Net-(PMOS4-S)") (class "Default")
      (node (ref "F4") (pin "2") (pinfunction "2_2") (pintype "bidirectional"))
      (node (ref "PMOS4") (pin "2") (pinfunction "S_2") (pintype "bidirectional"))
      (node (ref "RD5") (pin "1") (pinfunction "1_1") (pintype "passive"))
      (node (ref "RLED5") (pin "1") (pinfunction "1_1") (pintype "passive"))
      (node (ref "R_CIN4") (pin "1") (pinfunction "1_1") (pintype "passive"))
    )
    (net (code "82") (name "Net-(PMOS5-D)") (class "Default")
      (node (ref "LED5") (pin "A") (pinfunction "A_A") (pintype "passive"))
      (node (ref "PMOS5") (pin "3") (pinfunction "D_3") (pintype "bidirectional"))
      (node (ref "RD5") (pin "2") (pinfunction "2_2") (pintype "passive"))
    )
    (net (code "83") (name "Net-(PMOS5-G)") (class "Default")
      (node (ref "PMOS5") (pin "1") (pinfunction "G_1") (pintype "bidirectional"))
      (node (ref "R_SGATE5") (pin "1") (pinfunction "1_1") (pintype "passive"))
    )
    (net (code "84") (name "Net-(PMOS5-S)") (class "Default")
      (node (ref "F5") (pin "2") (pinfunction "2_2") (pintype "bidirectional"))
      (node (ref "PMOS5") (pin "2") (pinfunction "S_2") (pintype "bidirectional"))
      (node (ref "RD6") (pin "1") (pinfunction "1_1") (pintype "passive"))
      (node (ref "RLED6") (pin "1") (pinfunction "1_1") (pintype "passive"))
      (node (ref "R_CIN5") (pin "1") (pinfunction "1_1") (pintype "passive"))
    )
    (net (code "85") (name "Net-(PMOS6-D)") (class "Default")
      (node (ref "LED6") (pin "A") (pinfunction "A_A") (pintype "passive"))
      (node (ref "PMOS6") (pin "3") (pinfunction "D_3") (pintype "bidirectional"))
      (node (ref "RD6") (pin "2") (pinfunction "2_2") (pintype "passive"))
    )
    (net (code "86") (name "Net-(PMOS6-G)") (class "Default")
      (node (ref "PMOS6") (pin "1") (pinfunction "G_1") (pintype "bidirectional"))
      (node (ref "R_SGATE6") (pin "1") (pinfunction "1_1") (pintype "passive"))
    )
    (net (code "87") (name "Net-(PMOS6-S)") (class "Default")
      (node (ref "F6") (pin "2") (pinfunction "2_2") (pintype "bidirectional"))
      (node (ref "PMOS6") (pin "2") (pinfunction "S_2") (pintype "bidirectional"))
      (node (ref "RD7") (pin "1") (pinfunction "1_1") (pintype "passive"))
      (node (ref "RLED7") (pin "1") (pinfunction "1_1") (pintype "passive"))
      (node (ref "R_CIN6") (pin "1") (pinfunction "1_1") (pintype "passive"))
    )
    (net (code "88") (name "Net-(PMOS7-D)") (class "Default")
      (node (ref "LED7") (pin "A") (pinfunction "A_A") (pintype "passive"))
      (node (ref "PMOS7") (pin "3") (pinfunction "D_3") (pintype "bidirectional"))
      (node (ref "RD7") (pin "2") (pinfunction "2_2") (pintype "passive"))
    )
    (net (code "89") (name "Net-(PMOS7-G)") (class "Default")
      (node (ref "PMOS7") (pin "1") (pinfunction "G_1") (pintype "bidirectional"))
      (node (ref "R_SGATE7") (pin "1") (pinfunction "1_1") (pintype "passive"))
    )
    (net (code "90") (name "Net-(PMOS7-S)") (class "Default")
      (node (ref "F7") (pin "2") (pinfunction "2_2") (pintype "bidirectional"))
      (node (ref "PMOS7") (pin "2") (pinfunction "S_2") (pintype "bidirectional"))
      (node (ref "RD8") (pin "1") (pinfunction "1_1") (pintype "passive"))
      (node (ref "RLED8") (pin "1") (pinfunction "1_1") (pintype "passive"))
      (node (ref "R_CIN7") (pin "1") (pinfunction "1_1") (pintype "passive"))
    )
    (net (code "91") (name "Net-(PMOS8-D)") (class "Default")
      (node (ref "LED8") (pin "A") (pinfunction "A_A") (pintype "passive"))
      (node (ref "PMOS8") (pin "3") (pinfunction "D_3") (pintype "bidirectional"))
      (node (ref "RD8") (pin "2") (pinfunction "2_2") (pintype "passive"))
    )
    (net (code "92") (name "Net-(PMOS8-G)") (class "Default")
      (node (ref "PMOS8") (pin "1") (pinfunction "G_1") (pintype "bidirectional"))
      (node (ref "R_SGATE8") (pin "1") (pinfunction "1_1") (pintype "passive"))
    )
    (net (code "93") (name "Net-(PMOS8-S)") (class "Default")
      (node (ref "F8") (pin "2") (pinfunction "2_2") (pintype "bidirectional"))
      (node (ref "PMOS8") (pin "2") (pinfunction "S_2") (pintype "bidirectional"))
      (node (ref "RD9") (pin "1") (pinfunction "1_1") (pintype "passive"))
      (node (ref "RLED9") (pin "1") (pinfunction "1_1") (pintype "passive"))
      (node (ref "R_CIN8") (pin "1") (pinfunction "1_1") (pintype "passive"))
    )
    (net (code "94") (name "Net-(PMOS9-D)") (class "Default")
      (node (ref "LED9") (pin "A") (pinfunction "A_A") (pintype "passive"))
      (node (ref "PMOS9") (pin "3") (pinfunction "D_3") (pintype "bidirectional"))
      (node (ref "RD9") (pin "2") (pinfunction "2_2") (pintype "passive"))
    )
    (net (code "95") (name "Net-(PMOS9-G)") (class "Default")
      (node (ref "PMOS9") (pin "1") (pinfunction "G_1") (pintype "bidirectional"))
      (node (ref "R_SGATE9") (pin "1") (pinfunction "1_1") (pintype "passive"))
    )
    (net (code "96") (name "Net-(PMOS9-S)") (class "Default")
      (node (ref "F9") (pin "2") (pinfunction "2_2") (pintype "bidirectional"))
      (node (ref "PMOS9") (pin "2") (pinfunction "S_2") (pintype "bidirectional"))
      (node (ref "RD10") (pin "1") (pinfunction "1_1") (pintype "passive"))
      (node (ref "RLED10") (pin "1") (pinfunction "1_1") (pintype "passive"))
      (node (ref "R_CIN9") (pin "1") (pinfunction "1_1") (pintype "passive"))
    )
    (net (code "97") (name "Net-(PMOS10-D)") (class "Default")
      (node (ref "LED10") (pin "A") (pinfunction "A_A") (pintype "passive"))
      (node (ref "PMOS10") (pin "3") (pinfunction "D_3") (pintype "bidirectional"))
      (node (ref "RD10") (pin "2") (pinfunction "2_2") (pintype "passive"))
    )
    (net (code "98") (name "Net-(PMOS10-G)") (class "Default")
      (node (ref "PMOS10") (pin "1") (pinfunction "G_1") (pintype "bidirectional"))
      (node (ref "R_SGATE10") (pin "1") (pinfunction "1_1") (pintype "passive"))
    )
    (net (code "99") (name "Net-(PMOS10-S)") (class "Default")
      (node (ref "F10") (pin "2") (pinfunction "2_2") (pintype "bidirectional"))
      (node (ref "PMOS10") (pin "2") (pinfunction "S_2") (pintype "bidirectional"))
      (node (ref "RD11") (pin "1") (pinfunction "1_1") (pintype "passive"))
      (node (ref "RLED11") (pin "1") (pinfunction "1_1") (pintype "passive"))
      (node (ref "R_CIN10") (pin "1") (pinfunction "1_1") (pintype "passive"))
    )
    (net (code "100") (name "Net-(PMOS11-D)") (class "Default")
      (node (ref "LED11") (pin "A") (pinfunction "A_A") (pintype "passive"))
      (node (ref "PMOS11") (pin "3") (pinfunction "D_3") (pintype "bidirectional"))
      (node (ref "RD11") (pin "2") (pinfunction "2_2") (pintype "passive"))
    )
    (net (code "101") (name "Net-(PMOS11-G)") (class "Default")
      (node (ref "PMOS11") (pin "1") (pinfunction "G_1") (pintype "bidirectional"))
      (node (ref "R_SGATE11") (pin "1") (pinfunction "1_1") (pintype "passive"))
    )
    (net (code "102") (name "Net-(PMOS11-S)") (class "Default")
      (node (ref "F11") (pin "2") (pinfunction "2_2") (pintype "bidirectional"))
      (node (ref "PMOS11") (pin "2") (pinfunction "S_2") (pintype "bidirectional"))
      (node (ref "RD12") (pin "1") (pinfunction "1_1") (pintype "passive"))
      (node (ref "RLED12") (pin "1") (pinfunction "1_1") (pintype "passive"))
      (node (ref "R_CIN11") (pin "1") (pinfunction "1_1") (pintype "passive"))
    )
    (net (code "103") (name "Net-(PMOS12-D)") (class "Default")
      (node (ref "LED12") (pin "A") (pinfunction "A_A") (pintype "passive"))
      (node (ref "PMOS12") (pin "3") (pinfunction "D_3") (pintype "bidirectional"))
      (node (ref "RD12") (pin "2") (pinfunction "2_2") (pintype "passive"))
    )
    (net (code "104") (name "Net-(PMOS12-G)") (class "Default")
      (node (ref "PMOS12") (pin "1") (pinfunction "G_1") (pintype "bidirectional"))
      (node (ref "R_SGATE12") (pin "1") (pinfunction "1_1") (pintype "passive"))
    )
    (net (code "105") (name "Net-(PMOS12-S)") (class "Default")
      (node (ref "F12") (pin "2") (pinfunction "2_2") (pintype "bidirectional"))
      (node (ref "PMOS12") (pin "2") (pinfunction "S_2") (pintype "bidirectional"))
      (node (ref "R_CIN12") (pin "1") (pinfunction "1_1") (pintype "passive"))
    )
    (net (code "106") (name "Net-(U1-A1)") (class "Default")
      (node (ref "R_A1") (pin "1") (pinfunction "1_1") (pintype "passive"))
      (node (ref "U1") (pin "3") (pinfunction "A1_3") (pintype "input"))
    )
    (net (code "107") (name "Net-(U1-A2)") (class "Default")
      (node (ref "R_A2") (pin "1") (pinfunction "1_1") (pintype "passive"))
      (node (ref "U1") (pin "4") (pinfunction "A2_4") (pintype "input"))
    )
    (net (code "108") (name "Net-(U1-A3)") (class "Default")
      (node (ref "R_A3") (pin "1") (pinfunction "1_1") (pintype "passive"))
      (node (ref "U1") (pin "5") (pinfunction "A3_5") (pintype "input"))
    )
    (net (code "109") (name "Net-(U1-A4)") (class "Default")
      (node (ref "R_A4") (pin "1") (pinfunction "1_1") (pintype "passive"))
      (node (ref "U1") (pin "6") (pinfunction "A4_6") (pintype "output"))
    )
    (net (code "110") (name "Net-(U1-B1)") (class "Default")
      (node (ref "R_B1.") (pin "1") (pinfunction "1_1") (pintype "passive"))
      (node (ref "U1") (pin "14") (pinfunction "B1_14") (pintype "output"))
      (node (ref "U2") (pin "41") (pinfunction "SCKI_41") (pintype "input"))
    )
    (net (code "111") (name "Net-(U1-B2)") (class "Default")
      (node (ref "R_B2.") (pin "1") (pinfunction "1_1") (pintype "passive"))
      (node (ref "U1") (pin "13") (pinfunction "B2_13") (pintype "output"))
      (node (ref "U2") (pin "44") (pinfunction "CSBI_44") (pintype "input"))
    )
    (net (code "112") (name "Net-(U1-B3)") (class "Default")
      (node (ref "R_B3.") (pin "1") (pinfunction "1_1") (pintype "passive"))
      (node (ref "U1") (pin "12") (pinfunction "B3_12") (pintype "output"))
      (node (ref "U2") (pin "42") (pinfunction "SDI_42") (pintype "input"))
    )
    (net (code "113") (name "Net-(U1-B4)") (class "Default")
      (node (ref "R_B4.") (pin "1") (pinfunction "1_1") (pintype "passive"))
      (node (ref "R_VDD_VREG") (pin "2") (pinfunction "2_2") (pintype "passive"))
      (node (ref "U1") (pin "11") (pinfunction "B4_11") (pintype "input"))
      (node (ref "U2") (pin "43") (pinfunction "SDO_43") (pintype "open_collector"))
    )
    (net (code "114") (name "Net-(U2-GPIO1)") (class "Default")
      (node (ref "GPIO1") (pin "2") (pinfunction "2_2") (pintype "passive"))
      (node (ref "U2") (pin "35") (pinfunction "GPIO1_35") (pintype "bidirectional"))
    )
    (net (code "115") (name "Net-(U2-GPIO2)") (class "Default")
      (node (ref "GPIO2") (pin "2") (pinfunction "2_2") (pintype "passive"))
      (node (ref "U2") (pin "36") (pinfunction "GPIO2_36") (pintype "bidirectional"))
    )
    (net (code "116") (name "Net-(U2-V+)") (class "Default")
      (node (ref "R_V+") (pin "1") (pinfunction "1_1") (pintype "passive"))
      (node (ref "U2") (pin "1") (pinfunction "V+_1") (pintype "power_in"))
    )
    (net (code "117") (name "Net-(U2-WDTB)") (class "Default")
      (node (ref "R_WDTB") (pin "2") (pinfunction "2_2") (pintype "passive"))
      (node (ref "U2") (pin "34") (pinfunction "WDTB_34") (pintype "open_collector"))
    )
    (net (code "118") (name "unconnected-(X2F-KL-Pad6)") (class "Default")
      (node (ref "X2") (pin "6") (pinfunction "KL_6") (pintype "passive"))
    )
  )
)
